# 3_3V_Regulator.net
KiCad netlist of a schematic drawn in Altium Designer
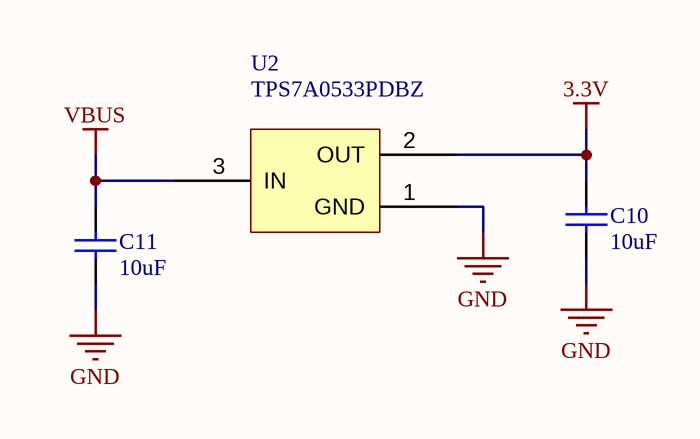
[diagram p0: 3.3V Regulator.SchDoc]

(export (version "E")
  (design (tool "Eeschema 10.0.6"))
  (components
    (comp (ref "C10") (value "10uF") (footprint "Capacitor 0402") (libsource (lib "x-io") (part "Capacitor")))
    (comp (ref "C11") (value "10uF") (footprint "Capacitor 0402") (libsource (lib "x-io") (part "Capacitor")))
    (comp (ref "U2")
      (value "TPS7A0533PDBZ")
      (footprint "SOT-23")
      (libsource (lib "x-io") (part "TPS7A0533PDBZ"))
    )
  )
  (nets
    (net (code "1") (name "3.3V") (class "Default")
      (node (ref "C10") (pin "2") (pinfunction "2_2") (pintype "passive"))
      (node (ref "U2") (pin "2") (pinfunction "OUT_2") (pintype "passive"))
    )
    (net (code "2") (name "GND") (class "Default")
      (node (ref "C10") (pin "1") (pinfunction "1_1") (pintype "passive"))
      (node (ref "C11") (pin "1") (pinfunction "1_1") (pintype "passive"))
      (node (ref "U2") (pin "1") (pinfunction "GND_1") (pintype "passive"))
    )
    (net (code "3") (name "VBUS") (class "Default")
      (node (ref "C11") (pin "2") (pinfunction "2_2") (pintype "passive"))
      (node (ref "U2") (pin "3") (pinfunction "IN_3") (pintype "passive"))
    )
  )
)
